# Parallel_CS_Prototype.net
KiCad netlist of a schematic drawn in EAGLE
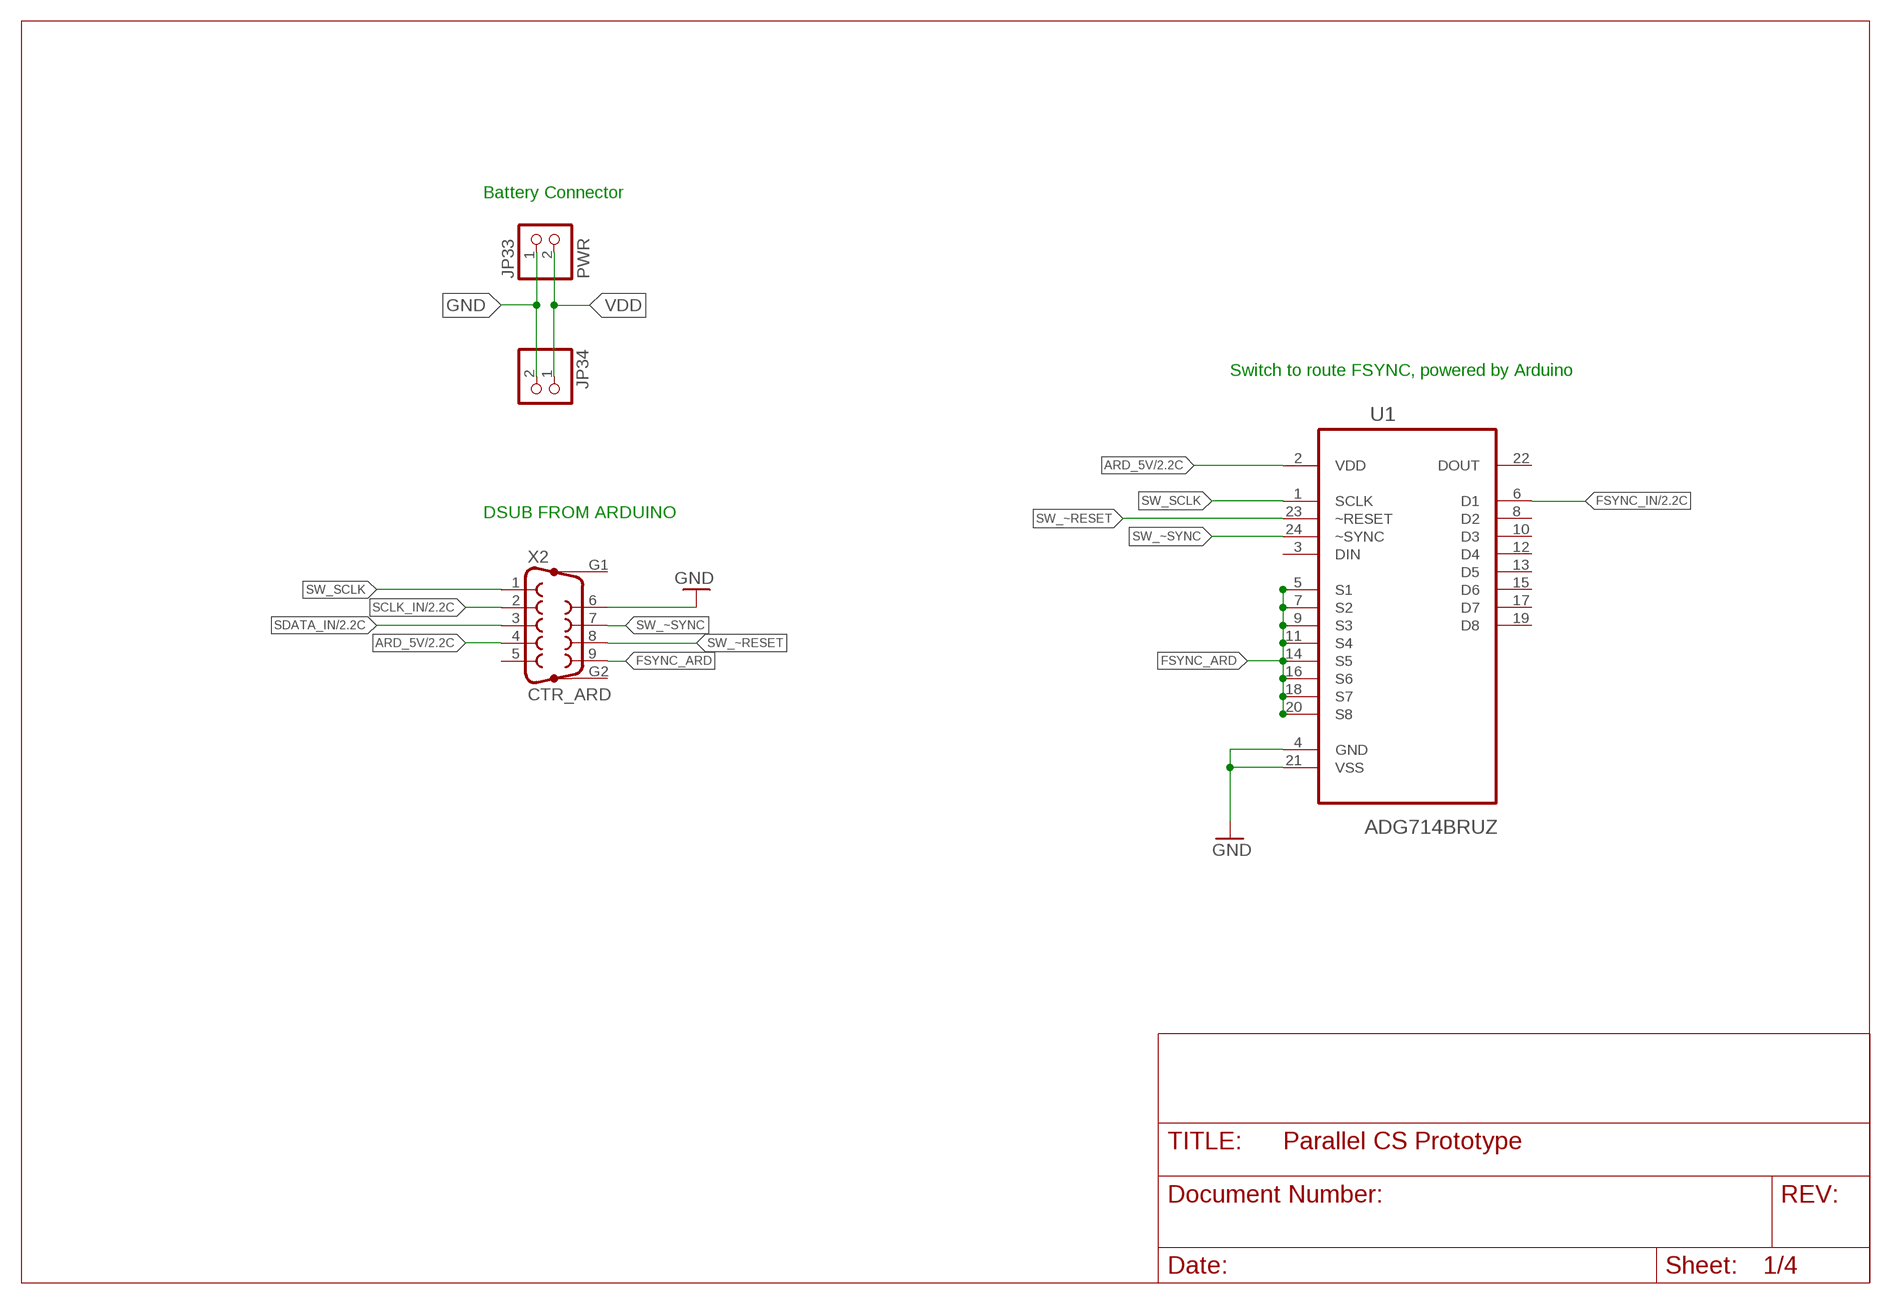
[diagram p0: schematic, sheet 1]
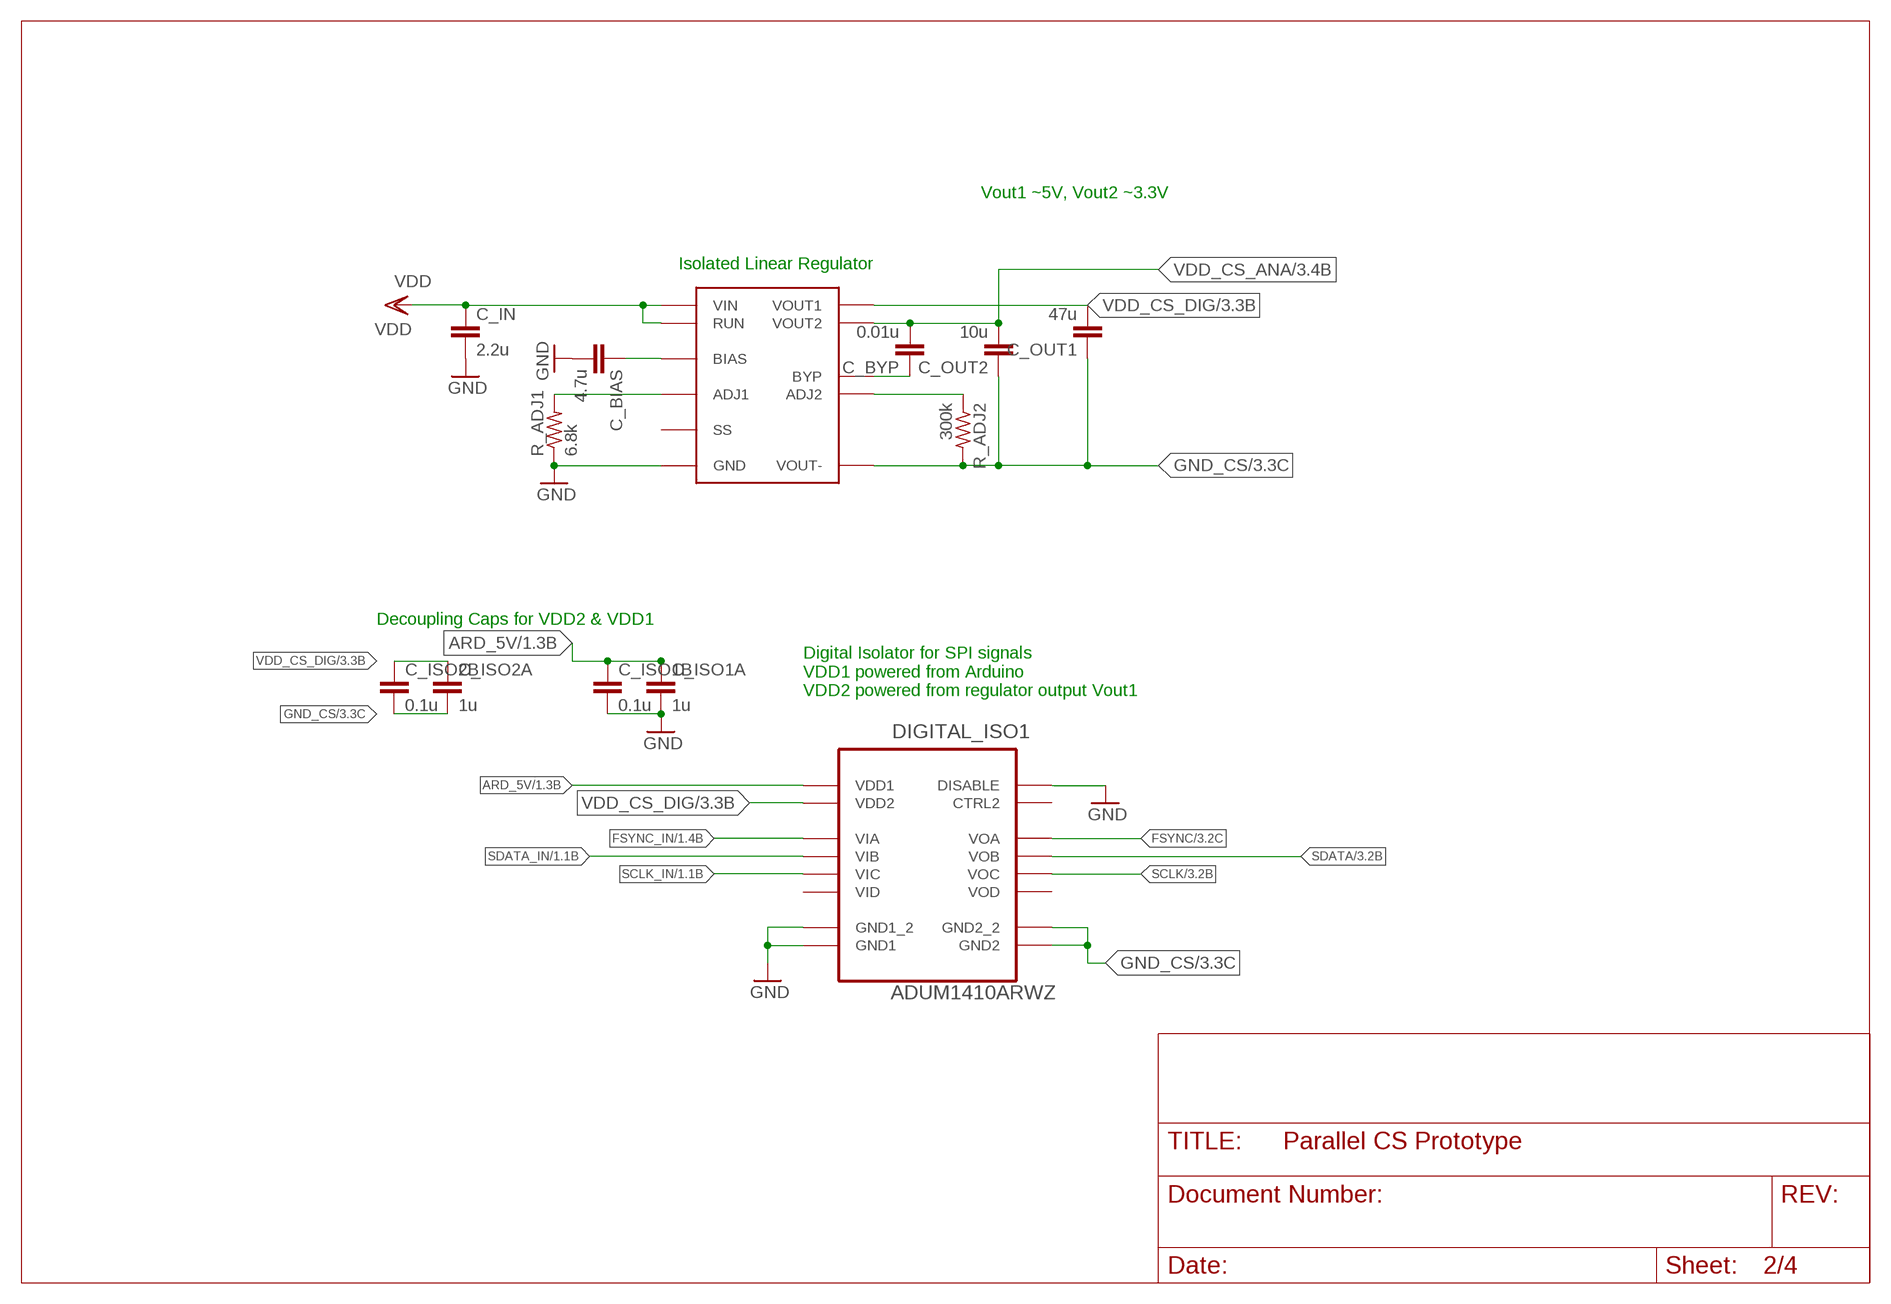
[diagram p1: schematic, sheet 2]
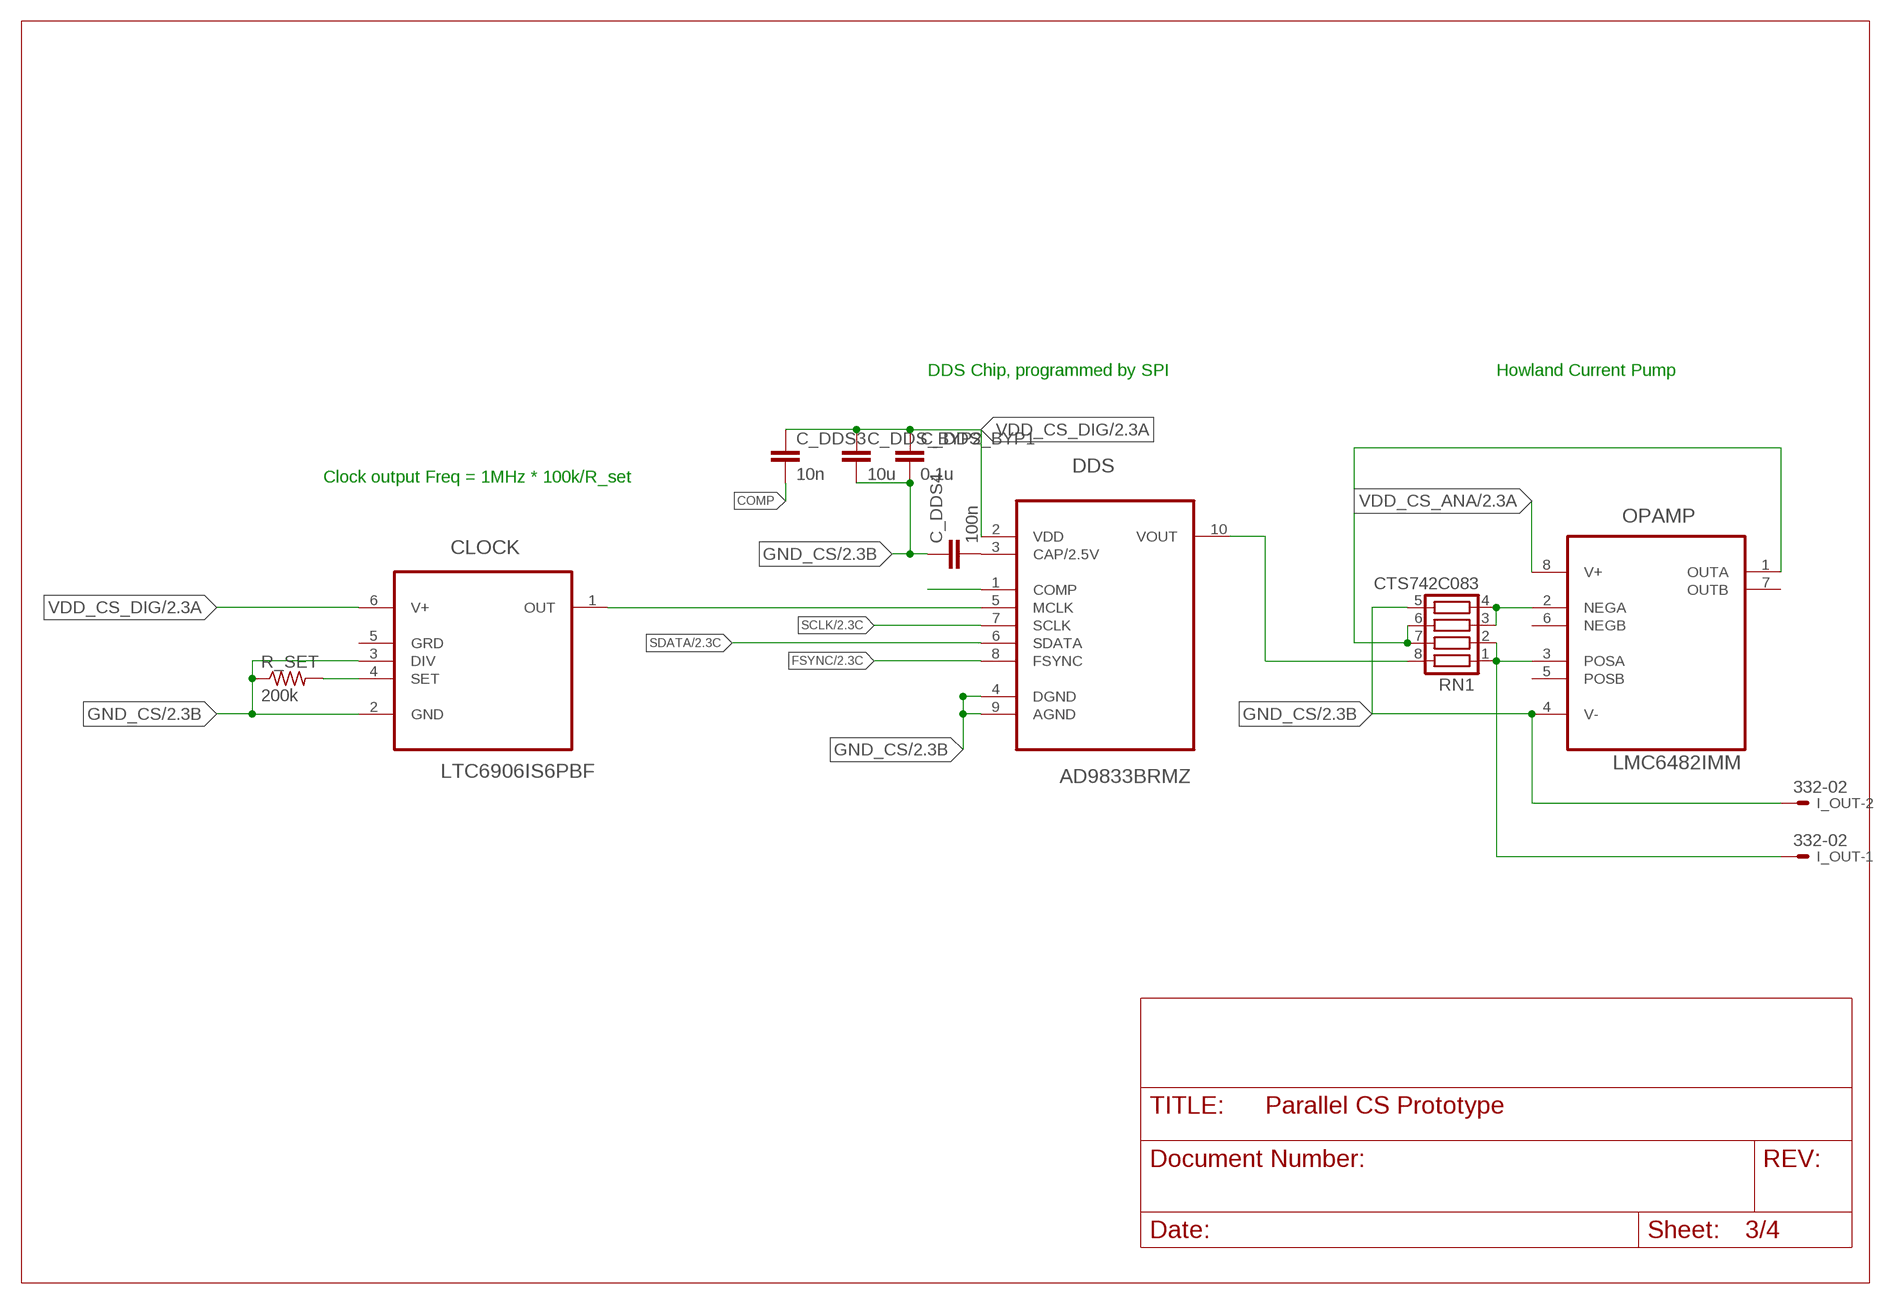
[diagram p2: schematic, sheet 3]
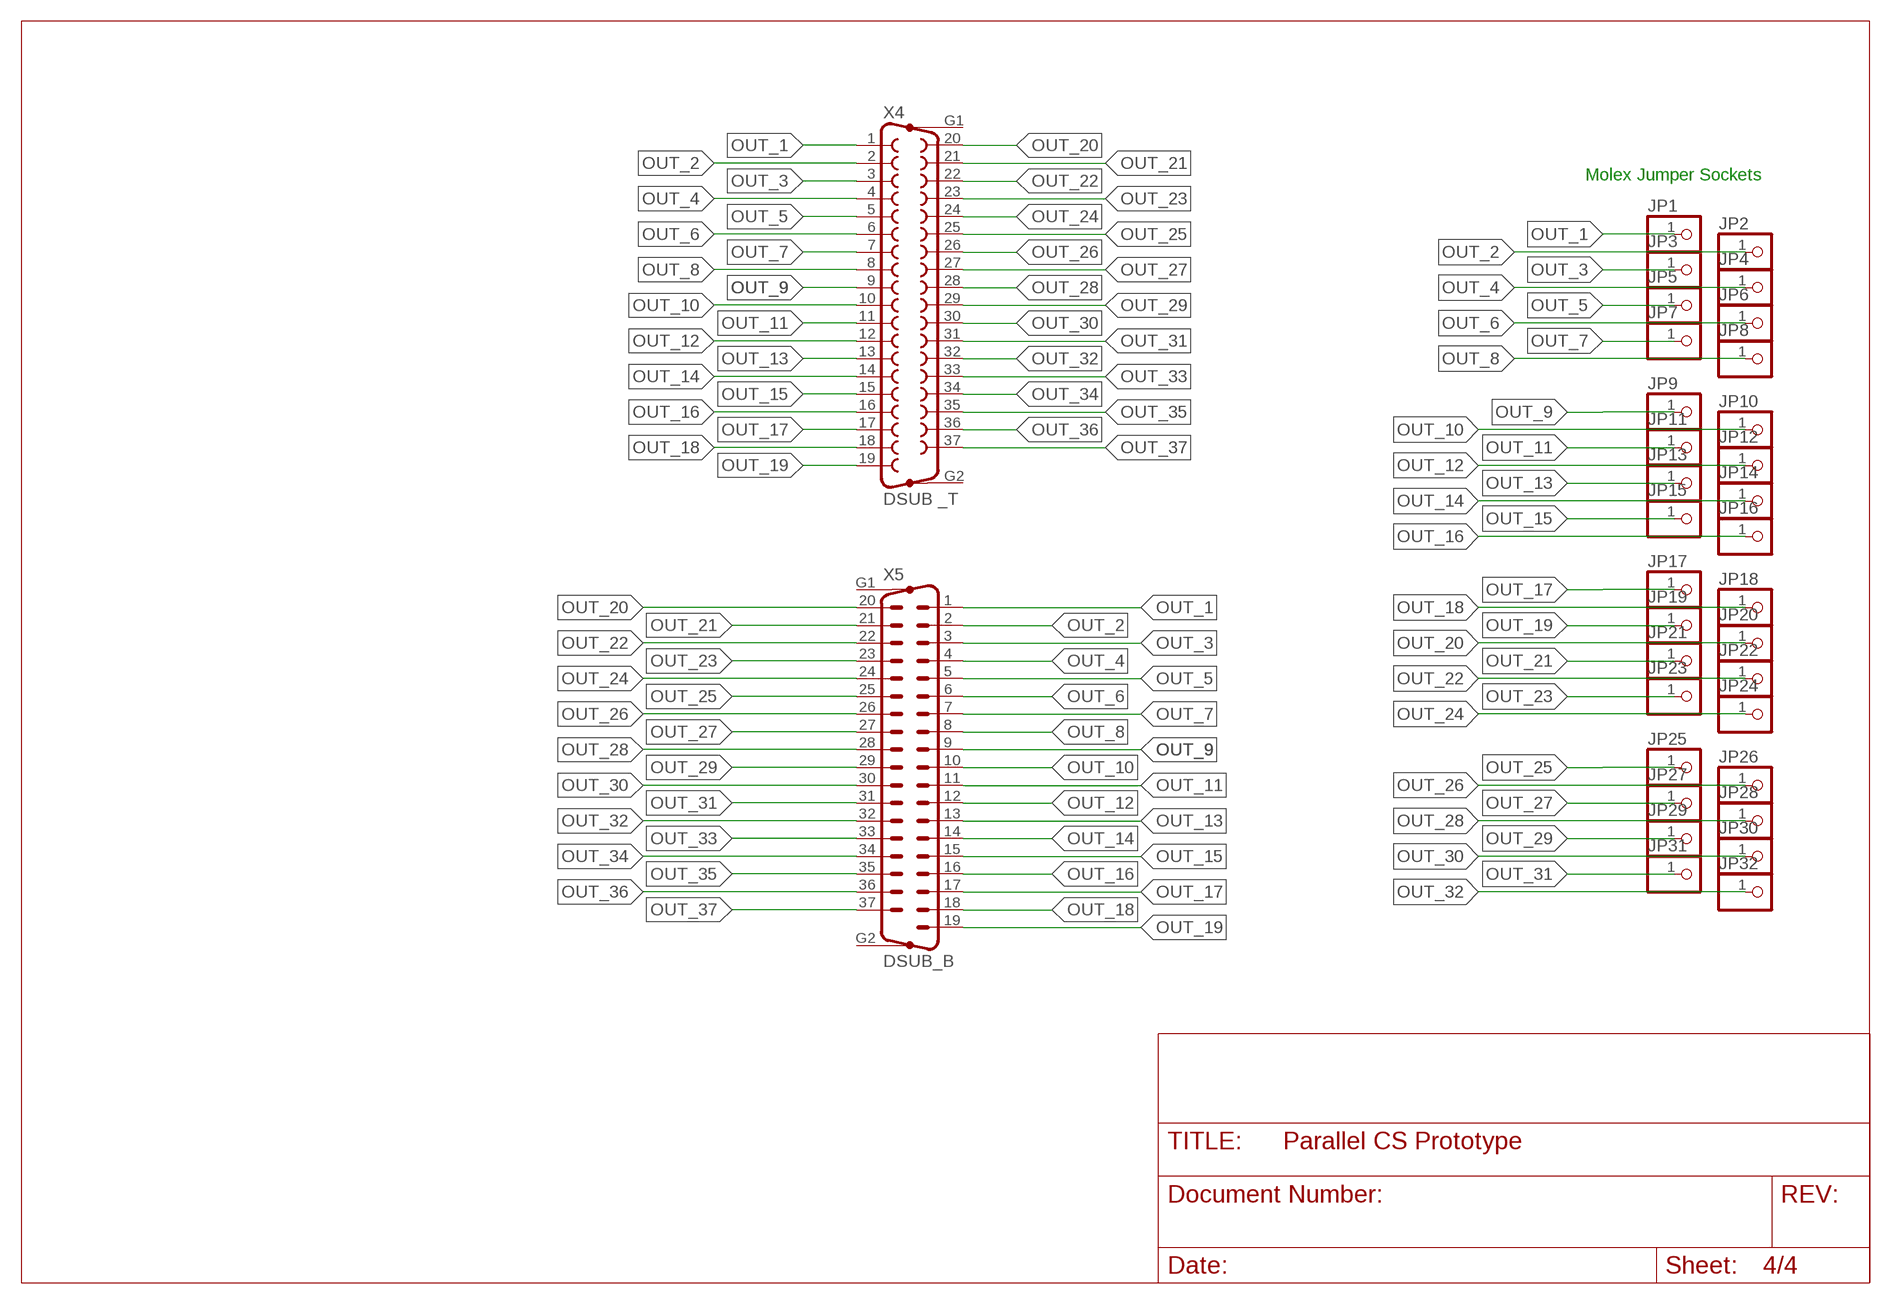
[diagram p3: schematic, sheet 4]

(export (version "E")
  (design (tool "Eeschema 10.0.6"))
  (components
    (comp (ref "C_BIAS")
      (value "4.7u")
      (footprint "eagle-import:C0805")
      (libsource (lib "eagle-import") (part "C-EUC0805"))
    )
    (comp (ref "C_BYP")
      (value "0.01u")
      (footprint "eagle-import:C0201")
      (libsource (lib "eagle-import") (part "C-EUC0201"))
    )
    (comp (ref "C_IN")
      (value "2.2u")
      (footprint "eagle-import:C0805")
      (libsource (lib "eagle-import") (part "C-EUC0805"))
    )
    (comp (ref "C_ISO1A")
      (value "1u")
      (footprint "eagle-import:C0402")
      (libsource (lib "eagle-import") (part "C-EUC0402"))
    )
    (comp (ref "C_ISO1B")
      (value "0.1u")
      (footprint "eagle-import:C0402")
      (libsource (lib "eagle-import") (part "C-EUC0402"))
    )
    (comp (ref "C_ISO2A")
      (value "1u")
      (footprint "eagle-import:C0402")
      (libsource (lib "eagle-import") (part "C-EUC0402"))
    )
    (comp (ref "C_ISO2B")
      (value "0.1u")
      (footprint "eagle-import:C0402")
      (libsource (lib "eagle-import") (part "C-EUC0402"))
    )
    (comp (ref "C_OUT1")
      (value "47u")
      (footprint "eagle-import:C0805")
      (libsource (lib "eagle-import") (part "C-EUC0805"))
    )
    (comp (ref "C_OUT2")
      (value "10u")
      (footprint "eagle-import:C0805")
      (libsource (lib "eagle-import") (part "C-EUC0805"))
    )
    (comp (ref "DIGITAL_ISO1")
      (value "ADUM1410ARWZ")
      (footprint "eagle-import:SOIC127P1032X265-16N")
      (libsource (lib "eagle-import") (part "ADUM1410ARWZ"))
    )
    (comp (ref "R_ADJ1")
      (value "6.8k")
      (footprint "eagle-import:R0201")
      (libsource (lib "eagle-import") (part "R-US_R0201"))
    )
    (comp (ref "R_ADJ2")
      (value "300k")
      (footprint "eagle-import:R0201")
      (libsource (lib "eagle-import") (part "R-US_R0201"))
    )
    (comp (ref "U$1")
      (value "LTM8048")
      (footprint "eagle-import:BGA-49")
      (libsource (lib "eagle-import") (part "LTM8048"))
    )
    (comp (ref "JP33")
      (value "PWR")
      (footprint "eagle-import:1X02")
      (libsource (lib "eagle-import") (part "pinhead_PINHD-1X2"))
    )
    (comp (ref "JP34")
      (value "PINHD-1X2")
      (footprint "eagle-import:1X02")
      (libsource (lib "eagle-import") (part "PINHD-1X2"))
    )
    (comp (ref "U1")
      (value "ADG714BRUZ")
      (footprint "eagle-import:SOP65P640X120-24N")
      (libsource (lib "eagle-import") (part "ADG714BRUZ"))
    )
    (comp (ref "X2")
      (value "CTR_ARD")
      (footprint "eagle-import:F09HP")
      (libsource (lib "eagle-import") (part "F09HP"))
    )
    (comp (ref "JP1")
      (value "PINHD-1X1")
      (footprint "eagle-import:1X01")
      (libsource (lib "eagle-import") (part "PINHD-1X1"))
    )
    (comp (ref "JP2")
      (value "PINHD-1X1")
      (footprint "eagle-import:1X01")
      (libsource (lib "eagle-import") (part "PINHD-1X1"))
    )
    (comp (ref "JP3")
      (value "PINHD-1X1")
      (footprint "eagle-import:1X01")
      (libsource (lib "eagle-import") (part "PINHD-1X1"))
    )
    (comp (ref "JP4")
      (value "PINHD-1X1")
      (footprint "eagle-import:1X01")
      (libsource (lib "eagle-import") (part "PINHD-1X1"))
    )
    (comp (ref "JP5")
      (value "PINHD-1X1")
      (footprint "eagle-import:1X01")
      (libsource (lib "eagle-import") (part "PINHD-1X1"))
    )
    (comp (ref "JP6")
      (value "PINHD-1X1")
      (footprint "eagle-import:1X01")
      (libsource (lib "eagle-import") (part "PINHD-1X1"))
    )
    (comp (ref "JP7")
      (value "PINHD-1X1")
      (footprint "eagle-import:1X01")
      (libsource (lib "eagle-import") (part "PINHD-1X1"))
    )
    (comp (ref "JP8")
      (value "PINHD-1X1")
      (footprint "eagle-import:1X01")
      (libsource (lib "eagle-import") (part "PINHD-1X1"))
    )
    (comp (ref "JP9")
      (value "PINHD-1X1")
      (footprint "eagle-import:1X01")
      (libsource (lib "eagle-import") (part "PINHD-1X1"))
    )
    (comp (ref "JP10")
      (value "PINHD-1X1")
      (footprint "eagle-import:1X01")
      (libsource (lib "eagle-import") (part "PINHD-1X1"))
    )
    (comp (ref "JP11")
      (value "PINHD-1X1")
      (footprint "eagle-import:1X01")
      (libsource (lib "eagle-import") (part "PINHD-1X1"))
    )
    (comp (ref "JP12")
      (value "PINHD-1X1")
      (footprint "eagle-import:1X01")
      (libsource (lib "eagle-import") (part "PINHD-1X1"))
    )
    (comp (ref "JP13")
      (value "PINHD-1X1")
      (footprint "eagle-import:1X01")
      (libsource (lib "eagle-import") (part "PINHD-1X1"))
    )
    (comp (ref "JP14")
      (value "PINHD-1X1")
      (footprint "eagle-import:1X01")
      (libsource (lib "eagle-import") (part "PINHD-1X1"))
    )
    (comp (ref "JP15")
      (value "PINHD-1X1")
      (footprint "eagle-import:1X01")
      (libsource (lib "eagle-import") (part "PINHD-1X1"))
    )
    (comp (ref "JP16")
      (value "PINHD-1X1")
      (footprint "eagle-import:1X01")
      (libsource (lib "eagle-import") (part "PINHD-1X1"))
    )
    (comp (ref "JP17")
      (value "PINHD-1X1")
      (footprint "eagle-import:1X01")
      (libsource (lib "eagle-import") (part "PINHD-1X1"))
    )
    (comp (ref "JP18")
      (value "PINHD-1X1")
      (footprint "eagle-import:1X01")
      (libsource (lib "eagle-import") (part "PINHD-1X1"))
    )
    (comp (ref "JP19")
      (value "PINHD-1X1")
      (footprint "eagle-import:1X01")
      (libsource (lib "eagle-import") (part "PINHD-1X1"))
    )
    (comp (ref "JP20")
      (value "PINHD-1X1")
      (footprint "eagle-import:1X01")
      (libsource (lib "eagle-import") (part "PINHD-1X1"))
    )
    (comp (ref "JP21")
      (value "PINHD-1X1")
      (footprint "eagle-import:1X01")
      (libsource (lib "eagle-import") (part "PINHD-1X1"))
    )
    (comp (ref "JP22")
      (value "PINHD-1X1")
      (footprint "eagle-import:1X01")
      (libsource (lib "eagle-import") (part "PINHD-1X1"))
    )
    (comp (ref "JP23")
      (value "PINHD-1X1")
      (footprint "eagle-import:1X01")
      (libsource (lib "eagle-import") (part "PINHD-1X1"))
    )
    (comp (ref "JP24")
      (value "PINHD-1X1")
      (footprint "eagle-import:1X01")
      (libsource (lib "eagle-import") (part "PINHD-1X1"))
    )
    (comp (ref "JP25")
      (value "PINHD-1X1")
      (footprint "eagle-import:1X01")
      (libsource (lib "eagle-import") (part "PINHD-1X1"))
    )
    (comp (ref "JP26")
      (value "PINHD-1X1")
      (footprint "eagle-import:1X01")
      (libsource (lib "eagle-import") (part "PINHD-1X1"))
    )
    (comp (ref "JP27")
      (value "PINHD-1X1")
      (footprint "eagle-import:1X01")
      (libsource (lib "eagle-import") (part "PINHD-1X1"))
    )
    (comp (ref "JP28")
      (value "PINHD-1X1")
      (footprint "eagle-import:1X01")
      (libsource (lib "eagle-import") (part "PINHD-1X1"))
    )
    (comp (ref "JP29")
      (value "PINHD-1X1")
      (footprint "eagle-import:1X01")
      (libsource (lib "eagle-import") (part "PINHD-1X1"))
    )
    (comp (ref "JP30")
      (value "PINHD-1X1")
      (footprint "eagle-import:1X01")
      (libsource (lib "eagle-import") (part "PINHD-1X1"))
    )
    (comp (ref "JP31")
      (value "PINHD-1X1")
      (footprint "eagle-import:1X01")
      (libsource (lib "eagle-import") (part "PINHD-1X1"))
    )
    (comp (ref "JP32")
      (value "PINHD-1X1")
      (footprint "eagle-import:1X01")
      (libsource (lib "eagle-import") (part "PINHD-1X1"))
    )
    (comp (ref "X4")
      (value "DSUB _T")
      (footprint "eagle-import:F37HP")
      (libsource (lib "eagle-import") (part "F37HP"))
    )
    (comp (ref "X5")
      (value "DSUB_B")
      (footprint "eagle-import:M37HP")
      (libsource (lib "eagle-import") (part "M37HP"))
    )
    (comp (ref "CLOCK")
      (value "LTC6906IS6PBF")
      (footprint "eagle-import:SOT95P280X100-6N")
      (fields (field (name "MPN") "LTC6906IS6#PBF"))
      (libsource (lib "eagle-import") (part "LTC6906IS6PBF"))
    )
    (comp (ref "C_DDS3")
      (value "10n")
      (footprint "eagle-import:C0402")
      (libsource (lib "eagle-import") (part "C-EUC0402"))
    )
    (comp (ref "C_DDS4")
      (value "100n")
      (footprint "eagle-import:C0402")
      (libsource (lib "eagle-import") (part "C-EUC0402"))
    )
    (comp (ref "C_DDS_BYP1")
      (value "0.1u")
      (footprint "eagle-import:C0402")
      (libsource (lib "eagle-import") (part "C-EUC0402"))
    )
    (comp (ref "C_DDS_BYP2")
      (value "10u")
      (footprint "eagle-import:C0402")
      (libsource (lib "eagle-import") (part "C-EUC0402"))
    )
    (comp (ref "DDS")
      (value "AD9833BRMZ")
      (footprint "eagle-import:SOP50P490X110-10N")
      (libsource (lib "eagle-import") (part "AD9833BRMZ"))
    )
    (comp (ref "I_OUT")
      (value "332-02")
      (footprint "eagle-import:332-02")
      (libsource (lib "eagle-import") (part "332-02"))
    )
    (comp (ref "OPAMP")
      (value "LMC6482IMM")
      (footprint "eagle-import:SOP65P490X109-8N")
      (libsource (lib "eagle-import") (part "LMC6482IMM"))
    )
    (comp (ref "RN1")
      (value "CTS742C083")
      (footprint "eagle-import:CTS742C083")
      (libsource (lib "eagle-import") (part "CTS742C083"))
    )
    (comp (ref "R_SET")
      (value "200k")
      (footprint "eagle-import:R0603")
      (libsource (lib "eagle-import") (part "R-US_R0603"))
    )
  )
  (nets
    (net (code "1") (name "ARD_5V") (class "Default")
      (node (ref "C_ISO1A") (pin "1") (pinfunction "1_1") (pintype "passive"))
      (node (ref "C_ISO1B") (pin "1") (pinfunction "1_1") (pintype "passive"))
      (node (ref "DIGITAL_ISO1") (pin "1") (pinfunction "VDD1_1") (pintype "power_in"))
      (node (ref "U1") (pin "2") (pinfunction "VDD_2") (pintype "power_in"))
      (node (ref "X2") (pin "4") (pinfunction "4_4") (pintype "passive"))
    )
    (net (code "2") (name "COMP") (class "Default")
      (node (ref "C_DDS3") (pin "2") (pinfunction "2_2") (pintype "passive"))
      (node (ref "DDS") (pin "1") (pinfunction "COMP_1") (pintype "passive"))
    )
    (net (code "3") (name "FSYNC") (class "Default")
      (node (ref "DDS") (pin "8") (pinfunction "FSYNC_8") (pintype "input"))
      (node (ref "DIGITAL_ISO1") (pin "14") (pinfunction "VOA_14") (pintype "passive"))
    )
    (net (code "4") (name "FSYNC_ARD") (class "Default")
      (node (ref "U1") (pin "11") (pinfunction "S4_11") (pintype "bidirectional"))
      (node (ref "U1") (pin "14") (pinfunction "S5_14") (pintype "bidirectional"))
      (node (ref "U1") (pin "16") (pinfunction "S6_16") (pintype "bidirectional"))
      (node (ref "U1") (pin "18") (pinfunction "S7_18") (pintype "bidirectional"))
      (node (ref "U1") (pin "20") (pinfunction "S8_20") (pintype "bidirectional"))
      (node (ref "U1") (pin "5") (pinfunction "S1_5") (pintype "bidirectional"))
      (node (ref "U1") (pin "7") (pinfunction "S2_7") (pintype "bidirectional"))
      (node (ref "U1") (pin "9") (pinfunction "S3_9") (pintype "bidirectional"))
      (node (ref "X2") (pin "9") (pinfunction "9_9") (pintype "passive"))
    )
    (net (code "5") (name "FSYNC_IN") (class "Default")
      (node (ref "DIGITAL_ISO1") (pin "3") (pinfunction "VIA_3") (pintype "passive"))
      (node (ref "U1") (pin "6") (pinfunction "D1_6") (pintype "bidirectional"))
    )
    (net (code "6") (name "GND") (class "Default")
      (node (ref "C_BIAS") (pin "2") (pinfunction "2_2") (pintype "passive"))
      (node (ref "C_IN") (pin "2") (pinfunction "2_2") (pintype "passive"))
      (node (ref "C_ISO1A") (pin "2") (pinfunction "2_2") (pintype "passive"))
      (node (ref "C_ISO1B") (pin "2") (pinfunction "2_2") (pintype "passive"))
      (node (ref "DIGITAL_ISO1") (pin "2") (pinfunction "GND1_2_2") (pintype "passive"))
      (node (ref "DIGITAL_ISO1") (pin "7") (pinfunction "DISABLE_7") (pintype "passive"))
      (node (ref "DIGITAL_ISO1") (pin "8") (pinfunction "GND1_8") (pintype "passive"))
      (node (ref "JP33") (pin "1") (pinfunction "1_1") (pintype "passive"))
      (node (ref "JP34") (pin "2") (pinfunction "2_2") (pintype "passive"))
      (node (ref "R_ADJ1") (pin "1") (pinfunction "1_1") (pintype "passive"))
      (node (ref "U$1") (pin "GND@1") (pinfunction "GND_GND@1") (pintype "bidirectional"))
      (node (ref "U$1") (pin "GND@10") (pinfunction "GND_GND@10") (pintype "bidirectional"))
      (node (ref "U$1") (pin "GND@11") (pinfunction "GND_GND@11") (pintype "bidirectional"))
      (node (ref "U$1") (pin "GND@12") (pinfunction "GND_GND@12") (pintype "bidirectional"))
      (node (ref "U$1") (pin "GND@13") (pinfunction "GND_GND@13") (pintype "bidirectional"))
      (node (ref "U$1") (pin "GND@14") (pinfunction "GND_GND@14") (pintype "bidirectional"))
      (node (ref "U$1") (pin "GND@15") (pinfunction "GND_GND@15") (pintype "bidirectional"))
      (node (ref "U$1") (pin "GND@16") (pinfunction "GND_GND@16") (pintype "bidirectional"))
      (node (ref "U$1") (pin "GND@2") (pinfunction "GND_GND@2") (pintype "bidirectional"))
      (node (ref "U$1") (pin "GND@3") (pinfunction "GND_GND@3") (pintype "bidirectional"))
      (node (ref "U$1") (pin "GND@4") (pinfunction "GND_GND@4") (pintype "bidirectional"))
      (node (ref "U$1") (pin "GND@5") (pinfunction "GND_GND@5") (pintype "bidirectional"))
      (node (ref "U$1") (pin "GND@6") (pinfunction "GND_GND@6") (pintype "bidirectional"))
      (node (ref "U$1") (pin "GND@7") (pinfunction "GND_GND@7") (pintype "bidirectional"))
      (node (ref "U$1") (pin "GND@8") (pinfunction "GND_GND@8") (pintype "bidirectional"))
      (node (ref "U$1") (pin "GND@9") (pinfunction "GND_GND@9") (pintype "bidirectional"))
      (node (ref "U1") (pin "21") (pinfunction "VSS_21") (pintype "power_in"))
      (node (ref "U1") (pin "4") (pinfunction "GND_4") (pintype "passive"))
      (node (ref "X2") (pin "6") (pinfunction "6_6") (pintype "passive"))
    )
    (net (code "7") (name "GND_CS") (class "Default")
      (node (ref "CLOCK") (pin "2") (pinfunction "GND_2") (pintype "passive"))
      (node (ref "CLOCK") (pin "3") (pinfunction "DIV_3") (pintype "input"))
      (node (ref "C_DDS4") (pin "1") (pinfunction "1_1") (pintype "passive"))
      (node (ref "C_DDS_BYP1") (pin "2") (pinfunction "2_2") (pintype "passive"))
      (node (ref "C_DDS_BYP2") (pin "2") (pinfunction "2_2") (pintype "passive"))
      (node (ref "C_ISO2A") (pin "2") (pinfunction "2_2") (pintype "passive"))
      (node (ref "C_ISO2B") (pin "2") (pinfunction "2_2") (pintype "passive"))
      (node (ref "C_OUT1") (pin "1") (pinfunction "1_1") (pintype "passive"))
      (node (ref "C_OUT2") (pin "1") (pinfunction "1_1") (pintype "passive"))
      (node (ref "DDS") (pin "4") (pinfunction "DGND_4") (pintype "passive"))
      (node (ref "DDS") (pin "9") (pinfunction "AGND_9") (pintype "passive"))
      (node (ref "DIGITAL_ISO1") (pin "15") (pinfunction "GND2_15") (pintype "passive"))
      (node (ref "DIGITAL_ISO1") (pin "9") (pinfunction "GND2_2_9") (pintype "passive"))
      (node (ref "I_OUT") (pin "2") (pinfunction "S_2") (pintype "passive"))
      (node (ref "OPAMP") (pin "4") (pinfunction "V-_4") (pintype "power_in"))
      (node (ref "RN1") (pin "5") (pinfunction "5_5") (pintype "passive"))
      (node (ref "R_ADJ2") (pin "2") (pinfunction "2_2") (pintype "passive"))
      (node (ref "R_SET") (pin "1") (pinfunction "1_1") (pintype "passive"))
      (node (ref "U$1") (pin "VOUT-@1") (pinfunction "VOUT-_VOUT-@1") (pintype "bidirectional"))
      (node (ref "U$1") (pin "VOUT-@2") (pinfunction "VOUT-_VOUT-@2") (pintype "bidirectional"))
      (node (ref "U$1") (pin "VOUT-@3") (pinfunction "VOUT-_VOUT-@3") (pintype "bidirectional"))
      (node (ref "U$1") (pin "VOUT-@4") (pinfunction "VOUT-_VOUT-@4") (pintype "bidirectional"))
      (node (ref "U$1") (pin "VOUT-@5") (pinfunction "VOUT-_VOUT-@5") (pintype "bidirectional"))
      (node (ref "U$1") (pin "VOUT-@6") (pinfunction "VOUT-_VOUT-@6") (pintype "bidirectional"))
      (node (ref "U$1") (pin "VOUT-@7") (pinfunction "VOUT-_VOUT-@7") (pintype "bidirectional"))
      (node (ref "U$1") (pin "VOUT-@8") (pinfunction "VOUT-_VOUT-@8") (pintype "bidirectional"))
      (node (ref "U$1") (pin "VOUT-@9") (pinfunction "VOUT-_VOUT-@9") (pintype "bidirectional"))
    )
    (net (code "8") (name "Net-(CLOCK-OUT)") (class "Default")
      (node (ref "CLOCK") (pin "1") (pinfunction "OUT_1") (pintype "output"))
      (node (ref "DDS") (pin "5") (pinfunction "MCLK_5") (pintype "input"))
    )
    (net (code "9") (name "Net-(CLOCK-SET)") (class "Default")
      (node (ref "CLOCK") (pin "4") (pinfunction "SET_4") (pintype "input"))
      (node (ref "R_SET") (pin "2") (pinfunction "2_2") (pintype "passive"))
    )
    (net (code "10") (name "Net-(C_BIAS-Pad1)") (class "Default")
      (node (ref "C_BIAS") (pin "1") (pinfunction "1_1") (pintype "passive"))
      (node (ref "U$1") (pin "BIAS") (pinfunction "BIAS_BIAS") (pintype "bidirectional"))
    )
    (net (code "11") (name "Net-(C_BYP-Pad1)") (class "Default")
      (node (ref "C_BYP") (pin "1") (pinfunction "1_1") (pintype "passive"))
      (node (ref "U$1") (pin "BYP") (pinfunction "BYP_BYP") (pintype "bidirectional"))
    )
    (net (code "12") (name "Net-(DDS-CAP{slash}2.5V)") (class "Default")
      (node (ref "C_DDS4") (pin "2") (pinfunction "2_2") (pintype "passive"))
      (node (ref "DDS") (pin "3") (pinfunction "CAP/2.5V_3") (pintype "passive"))
    )
    (net (code "13") (name "Net-(DDS-VOUT)") (class "Default")
      (node (ref "DDS") (pin "10") (pinfunction "VOUT_10") (pintype "output"))
      (node (ref "RN1") (pin "8") (pinfunction "8_8") (pintype "passive"))
    )
    (net (code "14") (name "Net-(I_OUTA-S)") (class "Default")
      (node (ref "I_OUT") (pin "1") (pinfunction "S_1") (pintype "passive"))
      (node (ref "OPAMP") (pin "3") (pinfunction "POSA_3") (pintype "input"))
      (node (ref "RN1") (pin "1") (pinfunction "1_1") (pintype "passive"))
      (node (ref "RN1") (pin "2") (pinfunction "2_2") (pintype "passive"))
    )
    (net (code "15") (name "Net-(OPAMP-NEGA)") (class "Default")
      (node (ref "OPAMP") (pin "2") (pinfunction "NEGA_2") (pintype "input"))
      (node (ref "RN1") (pin "3") (pinfunction "3_3") (pintype "passive"))
      (node (ref "RN1") (pin "4") (pinfunction "4_4") (pintype "passive"))
    )
    (net (code "16") (name "Net-(OPAMP-OUTA)") (class "Default")
      (node (ref "OPAMP") (pin "1") (pinfunction "OUTA_1") (pintype "output"))
      (node (ref "RN1") (pin "6") (pinfunction "6_6") (pintype "passive"))
      (node (ref "RN1") (pin "7") (pinfunction "7_7") (pintype "passive"))
    )
    (net (code "17") (name "Net-(R_ADJ1-Pad2)") (class "Default")
      (node (ref "R_ADJ1") (pin "2") (pinfunction "2_2") (pintype "passive"))
      (node (ref "U$1") (pin "ADJ1") (pinfunction "ADJ1_ADJ1") (pintype "bidirectional"))
    )
    (net (code "18") (name "Net-(R_ADJ2-Pad1)") (class "Default")
      (node (ref "R_ADJ2") (pin "1") (pinfunction "1_1") (pintype "passive"))
      (node (ref "U$1") (pin "ADJ2") (pinfunction "ADJ2_ADJ2") (pintype "bidirectional"))
    )
    (net (code "19") (name "OUT_1") (class "Default")
      (node (ref "JP1") (pin "1") (pinfunction "1_1") (pintype "passive"))
      (node (ref "X4") (pin "1") (pinfunction "1_1") (pintype "passive"))
      (node (ref "X5") (pin "1") (pinfunction "1_1") (pintype "passive"))
    )
    (net (code "20") (name "OUT_2") (class "Default")
      (node (ref "JP2") (pin "1") (pinfunction "1_1") (pintype "passive"))
      (node (ref "X4") (pin "2") (pinfunction "2_2") (pintype "passive"))
      (node (ref "X5") (pin "2") (pinfunction "2_2") (pintype "passive"))
    )
    (net (code "21") (name "OUT_3") (class "Default")
      (node (ref "JP3") (pin "1") (pinfunction "1_1") (pintype "passive"))
      (node (ref "X4") (pin "3") (pinfunction "3_3") (pintype "passive"))
      (node (ref "X5") (pin "3") (pinfunction "3_3") (pintype "passive"))
    )
    (net (code "22") (name "OUT_4") (class "Default")
      (node (ref "JP4") (pin "1") (pinfunction "1_1") (pintype "passive"))
      (node (ref "X4") (pin "4") (pinfunction "4_4") (pintype "passive"))
      (node (ref "X5") (pin "4") (pinfunction "4_4") (pintype "passive"))
    )
    (net (code "23") (name "OUT_5") (class "Default")
      (node (ref "JP5") (pin "1") (pinfunction "1_1") (pintype "passive"))
      (node (ref "X4") (pin "5") (pinfunction "5_5") (pintype "passive"))
      (node (ref "X5") (pin "5") (pinfunction "5_5") (pintype "passive"))
    )
    (net (code "24") (name "OUT_6") (class "Default")
      (node (ref "JP6") (pin "1") (pinfunction "1_1") (pintype "passive"))
      (node (ref "X4") (pin "6") (pinfunction "6_6") (pintype "passive"))
      (node (ref "X5") (pin "6") (pinfunction "6_6") (pintype "passive"))
    )
    (net (code "25") (name "OUT_7") (class "Default")
      (node (ref "JP7") (pin "1") (pinfunction "1_1") (pintype "passive"))
      (node (ref "X4") (pin "7") (pinfunction "7_7") (pintype "passive"))
      (node (ref "X5") (pin "7") (pinfunction "7_7") (pintype "passive"))
    )
    (net (code "26") (name "OUT_8") (class "Default")
      (node (ref "JP8") (pin "1") (pinfunction "1_1") (pintype "passive"))
      (node (ref "X4") (pin "8") (pinfunction "8_8") (pintype "passive"))
      (node (ref "X5") (pin "8") (pinfunction "8_8") (pintype "passive"))
    )
    (net (code "27") (name "OUT_9") (class "Default")
      (node (ref "JP9") (pin "1") (pinfunction "1_1") (pintype "passive"))
      (node (ref "X4") (pin "9") (pinfunction "9_9") (pintype "passive"))
      (node (ref "X5") (pin "9") (pinfunction "9_9") (pintype "passive"))
    )
    (net (code "28") (name "OUT_10") (class "Default")
      (node (ref "JP10") (pin "1") (pinfunction "1_1") (pintype "passive"))
      (node (ref "X4") (pin "10") (pinfunction "10_10") (pintype "passive"))
      (node (ref "X5") (pin "10") (pinfunction "10_10") (pintype "passive"))
    )
    (net (code "29") (name "OUT_11") (class "Default")
      (node (ref "JP11") (pin "1") (pinfunction "1_1") (pintype "passive"))
      (node (ref "X4") (pin "11") (pinfunction "11_11") (pintype "passive"))
      (node (ref "X5") (pin "11") (pinfunction "11_11") (pintype "passive"))
    )
    (net (code "30") (name "OUT_12") (class "Default")
      (node (ref "JP12") (pin "1") (pinfunction "1_1") (pintype "passive"))
      (node (ref "X4") (pin "12") (pinfunction "12_12") (pintype "passive"))
      (node (ref "X5") (pin "12") (pinfunction "12_12") (pintype "passive"))
    )
    (net (code "31") (name "OUT_13") (class "Default")
      (node (ref "JP13") (pin "1") (pinfunction "1_1") (pintype "passive"))
      (node (ref "X4") (pin "13") (pinfunction "13_13") (pintype "passive"))
      (node (ref "X5") (pin "13") (pinfunction "13_13") (pintype "passive"))
    )
    (net (code "32") (name "OUT_14") (class "Default")
      (node (ref "JP14") (pin "1") (pinfunction "1_1") (pintype "passive"))
      (node (ref "X4") (pin "14") (pinfunction "14_14") (pintype "passive"))
      (node (ref "X5") (pin "14") (pinfunction "14_14") (pintype "passive"))
    )
    (net (code "33") (name "OUT_15") (class "Default")
      (node (ref "JP15") (pin "1") (pinfunction "1_1") (pintype "passive"))
      (node (ref "X4") (pin "15") (pinfunction "15_15") (pintype "passive"))
      (node (ref "X5") (pin "15") (pinfunction "15_15") (pintype "passive"))
    )
    (net (code "34") (name "OUT_16") (class "Default")
      (node (ref "JP16") (pin "1") (pinfunction "1_1") (pintype "passive"))
      (node (ref "X4") (pin "16") (pinfunction "16_16") (pintype "passive"))
      (node (ref "X5") (pin "16") (pinfunction "16_16") (pintype "passive"))
    )
    (net (code "35") (name "OUT_17") (class "Default")
      (node (ref "JP17") (pin "1") (pinfunction "1_1") (pintype "passive"))
      (node (ref "X4") (pin "17") (pinfunction "17_17") (pintype "passive"))
      (node (ref "X5") (pin "17") (pinfunction "17_17") (pintype "passive"))
    )
    (net (code "36") (name "OUT_18") (class "Default")
      (node (ref "JP18") (pin "1") (pinfunction "1_1") (pintype "passive"))
      (node (ref "X4") (pin "18") (pinfunction "18_18") (pintype "passive"))
      (node (ref "X5") (pin "18") (pinfunction "18_18") (pintype "passive"))
    )
    (net (code "37") (name "OUT_19") (class "Default")
      (node (ref "JP19") (pin "1") (pinfunction "1_1") (pintype "passive"))
      (node (ref "X4") (pin "19") (pinfunction "19_19") (pintype "passive"))
      (node (ref "X5") (pin "19") (pinfunction "19_19") (pintype "passive"))
    )
    (net (code "38") (name "OUT_20") (class "Default")
      (node (ref "JP20") (pin "1") (pinfunction "1_1") (pintype "passive"))
      (node (ref "X4") (pin "20") (pinfunction "20_20") (pintype "passive"))
      (node (ref "X5") (pin "20") (pinfunction "20_20") (pintype "passive"))
    )
    (net (code "39") (name "OUT_21") (class "Default")
      (node (ref "JP21") (pin "1") (pinfunction "1_1") (pintype "passive"))
      (node (ref "X4") (pin "21") (pinfunction "21_21") (pintype "passive"))
      (node (ref "X5") (pin "21") (pinfunction "21_21") (pintype "passive"))
    )
    (net (code "40") (name "OUT_22") (class "Default")
      (node (ref "JP22") (pin "1") (pinfunction "1_1") (pintype "passive"))
      (node (ref "X4") (pin "22") (pinfunction "22_22") (pintype "passive"))
      (node (ref "X5") (pin "22") (pinfunction "22_22") (pintype "passive"))
    )
    (net (code "41") (name "OUT_23") (class "Default")
      (node (ref "JP23") (pin "1") (pinfunction "1_1") (pintype "passive"))
      (node (ref "X4") (pin "23") (pinfunction "23_23") (pintype "passive"))
      (node (ref "X5") (pin "23") (pinfunction "23_23") (pintype "passive"))
    )
    (net (code "42") (name "OUT_24") (class "Default")
      (node (ref "JP24") (pin "1") (pinfunction "1_1") (pintype "passive"))
      (node (ref "X4") (pin "24") (pinfunction "24_24") (pintype "passive"))
      (node (ref "X5") (pin "24") (pinfunction "24_24") (pintype "passive"))
    )
    (net (code "43") (name "OUT_25") (class "Default")
      (node (ref "JP25") (pin "1") (pinfunction "1_1") (pintype "passive"))
      (node (ref "X4") (pin "25") (pinfunction "25_25") (pintype "passive"))
      (node (ref "X5") (pin "25") (pinfunction "25_25") (pintype "passive"))
    )
    (net (code "44") (name "OUT_26") (class "Default")
      (node (ref "JP26") (pin "1") (pinfunction "1_1") (pintype "passive"))
      (node (ref "X4") (pin "26") (pinfunction "26_26") (pintype "passive"))
      (node (ref "X5") (pin "26") (pinfunction "26_26") (pintype "passive"))
    )
    (net (code "45") (name "OUT_27") (class "Default")
      (node (ref "JP27") (pin "1") (pinfunction "1_1") (pintype "passive"))
      (node (ref "X4") (pin "27") (pinfunction "27_27") (pintype "passive"))
      (node (ref "X5") (pin "27") (pinfunction "27_27") (pintype "passive"))
    )
    (net (code "46") (name "OUT_28") (class "Default")
      (node (ref "JP28") (pin "1") (pinfunction "1_1") (pintype "passive"))
      (node (ref "X4") (pin "28") (pinfunction "28_28") (pintype "passive"))
      (node (ref "X5") (pin "28") (pinfunction "28_28") (pintype "passive"))
    )
    (net (code "47") (name "OUT_29") (class "Default")
      (node (ref "JP29") (pin "1") (pinfunction "1_1") (pintype "passive"))
      (node (ref "X4") (pin "29") (pinfunction "29_29") (pintype "passive"))
      (node (ref "X5") (pin "29") (pinfunction "29_29") (pintype "passive"))
    )
    (net (code "48") (name "OUT_30") (class "Default")
      (node (ref "JP30") (pin "1") (pinfunction "1_1") (pintype "passive"))
      (node (ref "X4") (pin "30") (pinfunction "30_30") (pintype "passive"))
      (node (ref "X5") (pin "30") (pinfunction "30_30") (pintype "passive"))
    )
    (net (code "49") (name "OUT_31") (class "Default")
      (node (ref "JP31") (pin "1") (pinfunction "1_1") (pintype "passive"))
      (node (ref "X4") (pin "31") (pinfunction "31_31") (pintype "passive"))
      (node (ref "X5") (pin "31") (pinfunction "31_31") (pintype "passive"))
    )
    (net (code "50") (name "OUT_32") (class "Default")
      (node (ref "JP32") (pin "1") (pinfunction "1_1") (pintype "passive"))
      (node (ref "X4") (pin "32") (pinfunction "32_32") (pintype "passive"))
      (node (ref "X5") (pin "32") (pinfunction "32_32") (pintype "passive"))
    )
    (net (code "51") (name "OUT_33") (class "Default")
      (node (ref "X4") (pin "33") (pinfunction "33_33") (pintype "passive"))
      (node (ref "X5") (pin "33") (pinfunction "33_33") (pintype "passive"))
    )
    (net (code "52") (name "OUT_34") (class "Default")
      (node (ref "X4") (pin "34") (pinfunction "34_34") (pintype "passive"))
      (node (ref "X5") (pin "34") (pinfunction "34_34") (pintype "passive"))
    )
    (net (code "53") (name "OUT_35") (class "Default")
      (node (ref "X4") (pin "35") (pinfunction "35_35") (pintype "passive"))
      (node (ref "X5") (pin "35") (pinfunction "35_35") (pintype "passive"))
    )
    (net (code "54") (name "OUT_36") (class "Default")
      (node (ref "X4") (pin "36") (pinfunction "36_36") (pintype "passive"))
      (node (ref "X5") (pin "36") (pinfunction "36_36") (pintype "passive"))
    )
    (net (code "55") (name "OUT_37") (class "Default")
      (node (ref "X4") (pin "37") (pinfunction "37_37") (pintype "passive"))
      (node (ref "X5") (pin "37") (pinfunction "37_37") (pintype "passive"))
    )
    (net (code "56") (name "SCLK") (class "Default")
      (node (ref "DDS") (pin "7") (pinfunction "SCLK_7") (pintype "input"))
      (node (ref "DIGITAL_ISO1") (pin "12") (pinfunction "VOC_12") (pintype "passive"))
    )
    (net (code "57") (name "SCLK_IN") (class "Default")
      (node (ref "DIGITAL_ISO1") (pin "5") (pinfunction "VIC_5") (pintype "passive"))
      (node (ref "X2") (pin "2") (pinfunction "2_2") (pintype "passive"))
    )
    (net (code "58") (name "SDATA") (class "Default")
      (node (ref "DDS") (pin "6") (pinfunction "SDATA_6") (pintype "input"))
      (node (ref "DIGITAL_ISO1") (pin "13") (pinfunction "VOB_13") (pintype "passive"))
    )
    (net (code "59") (name "SDATA_IN") (class "Default")
      (node (ref "DIGITAL_ISO1") (pin "4") (pinfunction "VIB_4") (pintype "passive"))
      (node (ref "X2") (pin "3") (pinfunction "3_3") (pintype "passive"))
    )
    (net (code "60") (name "SW_SCLK") (class "Default")
      (node (ref "U1") (pin "1") (pinfunction "SCLK_1") (pintype "input"))
      (node (ref "X2") (pin "1") (pinfunction "1_1") (pintype "passive"))
    )
    (net (code "61") (name "SW_~{RESET}") (class "Default")
      (node (ref "U1") (pin "23") (pinfunction "~{RESET}_23") (pintype "input"))
      (node (ref "X2") (pin "8") (pinfunction "8_8") (pintype "passive"))
    )
    (net (code "62") (name "SW_~{SYNC}") (class "Default")
      (node (ref "U1") (pin "24") (pinfunction "~{SYNC}_24") (pintype "input"))
      (node (ref "X2") (pin "7") (pinfunction "7_7") (pintype "passive"))
    )
    (net (code "63") (name "VDD") (class "Default")
      (node (ref "C_IN") (pin "1") (pinfunction "1_1") (pintype "passive"))
      (node (ref "JP33") (pin "2") (pinfunction "2_2") (pintype "passive"))
      (node (ref "JP34") (pin "1") (pinfunction "1_1") (pintype "passive"))
      (node (ref "U$1") (pin "RUN") (pinfunction "RUN_RUN") (pintype "bidirectional"))
      (node (ref "U$1") (pin "VIN@1") (pinfunction "VIN_VIN@1") (pintype "bidirectional"))
      (node (ref "U$1") (pin "VIN@2") (pinfunction "VIN_VIN@2") (pintype "bidirectional"))
      (node (ref "U$1") (pin "VIN@3") (pinfunction "VIN_VIN@3") (pintype "bidirectional"))
      (node (ref "U$1") (pin "VIN@4") (pinfunction "VIN_VIN@4") (pintype "bidirectional"))
    )
    (net (code "64") (name "VDD_CS_ANA") (class "Default")
      (node (ref "C_BYP") (pin "2") (pinfunction "2_2") (pintype "passive"))
      (node (ref "C_OUT2") (pin "2") (pinfunction "2_2") (pintype "passive"))
      (node (ref "OPAMP") (pin "8") (pinfunction "V+_8") (pintype "power_in"))
      (node (ref "U$1") (pin "VOUT2@1") (pinfunction "VOUT2_VOUT2@1") (pintype "bidirectional"))
      (node (ref "U$1") (pin "VOUT2@2") (pinfunction "VOUT2_VOUT2@2") (pintype "bidirectional"))
      (node (ref "U$1") (pin "VOUT2@3") (pinfunction "VOUT2_VOUT2@3") (pintype "bidirectional"))
      (node (ref "U$1") (pin "VOUT2@4") (pinfunction "VOUT2_VOUT2@4") (pintype "bidirectional"))
    )
    (net (code "65") (name "VDD_CS_DIG") (class "Default")
      (node (ref "CLOCK") (pin "6") (pinfunction "V+_6") (pintype "power_in"))
      (node (ref "C_DDS3") (pin "1") (pinfunction "1_1") (pintype "passive"))
      (node (ref "C_DDS_BYP1") (pin "1") (pinfunction "1_1") (pintype "passive"))
      (node (ref "C_DDS_BYP2") (pin "1") (pinfunction "1_1") (pintype "passive"))
      (node (ref "C_ISO2A") (pin "1") (pinfunction "1_1") (pintype "passive"))
      (node (ref "C_ISO2B") (pin "1") (pinfunction "1_1") (pintype "passive"))
      (node (ref "C_OUT1") (pin "2") (pinfunction "2_2") (pintype "passive"))
      (node (ref "DDS") (pin "2") (pinfunction "VDD_2") (pintype "power_in"))
      (node (ref "DIGITAL_ISO1") (pin "16") (pinfunction "VDD2_16") (pintype "power_in"))
      (node (ref "U$1") (pin "VOUT1@1") (pinfunction "VOUT1_VOUT1@1") (pintype "bidirectional"))
      (node (ref "U$1") (pin "VOUT1@2") (pinfunction "VOUT1_VOUT1@2") (pintype "bidirectional"))
      (node (ref "U$1") (pin "VOUT1@3") (pinfunction "VOUT1_VOUT1@3") (pintype "bidirectional"))
      (node (ref "U$1") (pin "VOUT1@4") (pinfunction "VOUT1_VOUT1@4") (pintype "bidirectional"))
      (node (ref "U$1") (pin "VOUT1@5") (pinfunction "VOUT1_VOUT1@5") (pintype "bidirectional"))
      (node (ref "U$1") (pin "VOUT1@6") (pinfunction "VOUT1_VOUT1@6") (pintype "bidirectional"))
    )
    (net (code "66") (name "unconnected-(CLOCK-GRD-Pad5)") (class "Default")
      (node (ref "CLOCK") (pin "5") (pinfunction "GRD_5") (pintype "input"))
    )
    (net (code "67") (name "unconnected-(DIGITAL_ISO1-CTRL2-Pad10)") (class "Default")
      (node (ref "DIGITAL_ISO1") (pin "10") (pinfunction "CTRL2_10") (pintype "passive"))
    )
    (net (code "68") (name "unconnected-(DIGITAL_ISO1-VID-Pad6)") (class "Default")
      (node (ref "DIGITAL_ISO1") (pin "6") (pinfunction "VID_6") (pintype "passive"))
    )
    (net (code "69") (name "unconnected-(DIGITAL_ISO1-VOD-Pad11)") (class "Default")
      (node (ref "DIGITAL_ISO1") (pin "11") (pinfunction "VOD_11") (pintype "passive"))
    )
    (net (code "70") (name "unconnected-(OPAMP-NEGB-Pad6)") (class "Default")
      (node (ref "OPAMP") (pin "6") (pinfunction "NEGB_6") (pintype "input"))
    )
    (net (code "71") (name "unconnected-(OPAMP-OUTB-Pad7)") (class "Default")
      (node (ref "OPAMP") (pin "7") (pinfunction "OUTB_7") (pintype "output"))
    )
    (net (code "72") (name "unconnected-(OPAMP-POSB-Pad5)") (class "Default")
      (node (ref "OPAMP") (pin "5") (pinfunction "POSB_5") (pintype "input"))
    )
    (net (code "73") (name "unconnected-(U$1-PadSS)") (class "Default")
      (node (ref "U$1") (pin "SS") (pinfunction "SS_SS") (pintype "bidirectional"))
    )
    (net (code "74") (name "unconnected-(U1-D2-Pad8)") (class "Default")
      (node (ref "U1") (pin "8") (pinfunction "D2_8") (pintype "bidirectional"))
    )
    (net (code "75") (name "unconnected-(U1-D3-Pad10)") (class "Default")
      (node (ref "U1") (pin "10") (pinfunction "D3_10") (pintype "bidirectional"))
    )
    (net (code "76") (name "unconnected-(U1-D4-Pad12)") (class "Default")
      (node (ref "U1") (pin "12") (pinfunction "D4_12") (pintype "bidirectional"))
    )
    (net (code "77") (name "unconnected-(U1-D5-Pad13)") (class "Default")
      (node (ref "U1") (pin "13") (pinfunction "D5_13") (pintype "bidirectional"))
    )
    (net (code "78") (name "unconnected-(U1-D6-Pad15)") (class "Default")
      (node (ref "U1") (pin "15") (pinfunction "D6_15") (pintype "bidirectional"))
    )
    (net (code "79") (name "unconnected-(U1-D7-Pad17)") (class "Default")
      (node (ref "U1") (pin "17") (pinfunction "D7_17") (pintype "bidirectional"))
    )
    (net (code "80") (name "unconnected-(U1-D8-Pad19)") (class "Default")
      (node (ref "U1") (pin "19") (pinfunction "D8_19") (pintype "bidirectional"))
    )
    (net (code "81") (name "unconnected-(U1-DIN-Pad3)") (class "Default")
      (node (ref "U1") (pin "3") (pinfunction "DIN_3") (pintype "input"))
    )
    (net (code "82") (name "unconnected-(U1-DOUT-Pad22)") (class "Default")
      (node (ref "U1") (pin "22") (pinfunction "DOUT_22") (pintype "output"))
    )
    (net (code "83") (name "unconnected-(X2-Pad5)") (class "Default")
      (node (ref "X2") (pin "5") (pinfunction "5_5") (pintype "passive"))
    )
    (net (code "84") (name "unconnected-(X2-PadG1)") (class "Default")
      (node (ref "X2") (pin "G1") (pinfunction "G1_G1") (pintype "passive"))
    )
    (net (code "85") (name "unconnected-(X2-PadG2)") (class "Default")
      (node (ref "X2") (pin "G2") (pinfunction "G2_G2") (pintype "passive"))
    )
    (net (code "86") (name "unconnected-(X4-PadG1)") (class "Default")
      (node (ref "X4") (pin "G1") (pinfunction "G1_G1") (pintype "passive"))
    )
    (net (code "87") (name "unconnected-(X4-PadG2)") (class "Default")
      (node (ref "X4") (pin "G2") (pinfunction "G2_G2") (pintype "passive"))
    )
    (net (code "88") (name "unconnected-(X5-PadG1)") (class "Default")
      (node (ref "X5") (pin "G1") (pinfunction "G1_G1") (pintype "passive"))
    )
    (net (code "89") (name "unconnected-(X5-PadG2)") (class "Default")
      (node (ref "X5") (pin "G2") (pinfunction "G2_G2") (pintype "passive"))
    )
  )
)
